# Test_Points.net
KiCad netlist of a schematic drawn in Altium Designer
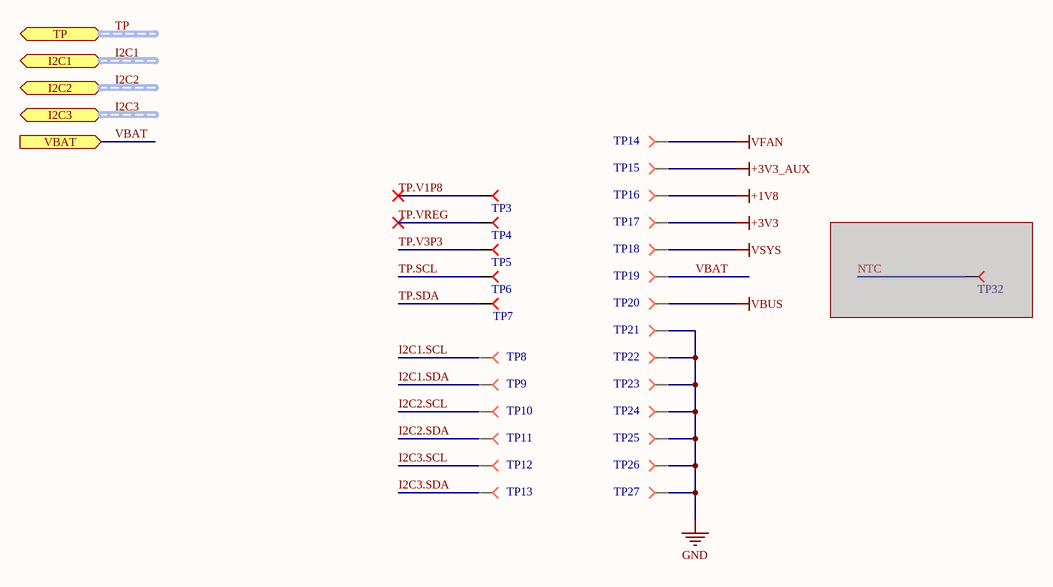
[diagram p0: Test_Points.SchDoc]

(export (version "E")
  (design (tool "Eeschema 10.0.6"))
  (components
    (comp (ref "TP3")
      (value "Test Point Pad")
      (footprint "Testpoint")
      (description "Test Point. There is nothing to buy or mount.")
      (libsource (lib "BLDC_Motor_Driver") (part "Test Point Pad"))
    )
    (comp (ref "TP4")
      (value "Test Point Pad")
      (footprint "Testpoint")
      (description "Test Point. There is nothing to buy or mount.")
      (libsource (lib "BLDC_Motor_Driver") (part "Test Point Pad"))
    )
    (comp (ref "TP5")
      (value "Test Point Pad")
      (footprint "Testpoint")
      (description "Test Point. There is nothing to buy or mount.")
      (libsource (lib "BLDC_Motor_Driver") (part "Test Point Pad"))
    )
    (comp (ref "TP6")
      (value "Test Point Pad")
      (footprint "Testpoint")
      (description "Test Point. There is nothing to buy or mount.")
      (libsource (lib "BLDC_Motor_Driver") (part "Test Point Pad"))
    )
    (comp (ref "TP7")
      (value "Test Point Pad")
      (footprint "Testpoint")
      (description "Test Point. There is nothing to buy or mount.")
      (libsource (lib "BLDC_Motor_Driver") (part "Test Point Pad"))
    )
    (comp (ref "TP8")
      (value "Test Point Pad")
      (footprint "Testpoint")
      (description "Test Point. There is nothing to buy or mount.")
      (libsource (lib "") (part "Test Point Pad_2"))
    )
    (comp (ref "TP9")
      (value "Test Point Pad")
      (footprint "Testpoint")
      (description "Test Point. There is nothing to buy or mount.")
      (libsource (lib "") (part "Test Point Pad_2"))
    )
    (comp (ref "TP10")
      (value "Test Point Pad")
      (footprint "Testpoint")
      (description "Test Point. There is nothing to buy or mount.")
      (libsource (lib "") (part "Test Point Pad_2"))
    )
    (comp (ref "TP11")
      (value "Test Point Pad")
      (footprint "Testpoint")
      (description "Test Point. There is nothing to buy or mount.")
      (libsource (lib "") (part "Test Point Pad_2"))
    )
    (comp (ref "TP12")
      (value "Test Point Pad")
      (footprint "Testpoint")
      (description "Test Point. There is nothing to buy or mount.")
      (libsource (lib "") (part "Test Point Pad_2"))
    )
    (comp (ref "TP13")
      (value "Test Point Pad")
      (footprint "Testpoint")
      (description "Test Point. There is nothing to buy or mount.")
      (libsource (lib "") (part "Test Point Pad_2"))
    )
    (comp (ref "TP14")
      (value "Test Point Pad")
      (footprint "Testpoint")
      (description "Test Point. There is nothing to buy or mount.")
      (libsource (lib "") (part "Test Point Pad_1"))
    )
    (comp (ref "TP15")
      (value "Test Point Pad")
      (footprint "Testpoint")
      (description "Test Point. There is nothing to buy or mount.")
      (libsource (lib "") (part "Test Point Pad_1"))
    )
    (comp (ref "TP16")
      (value "Test Point Pad")
      (footprint "Testpoint")
      (description "Test Point. There is nothing to buy or mount.")
      (libsource (lib "") (part "Test Point Pad_1"))
    )
    (comp (ref "TP17")
      (value "Test Point Pad")
      (footprint "Testpoint")
      (description "Test Point. There is nothing to buy or mount.")
      (libsource (lib "") (part "Test Point Pad_1"))
    )
    (comp (ref "TP18")
      (value "Test Point Pad")
      (footprint "Testpoint")
      (description "Test Point. There is nothing to buy or mount.")
      (libsource (lib "") (part "Test Point Pad_1"))
    )
    (comp (ref "TP19")
      (value "Test Point Pad")
      (footprint "Testpoint")
      (description "Test Point. There is nothing to buy or mount.")
      (libsource (lib "") (part "Test Point Pad_1"))
    )
    (comp (ref "TP20")
      (value "Test Point Pad")
      (footprint "Testpoint")
      (description "Test Point. There is nothing to buy or mount.")
      (libsource (lib "") (part "Test Point Pad_1"))
    )
    (comp (ref "TP21")
      (value "Test Point Pad")
      (footprint "Testpoint")
      (description "Test Point. There is nothing to buy or mount.")
      (libsource (lib "") (part "Test Point Pad_1"))
    )
    (comp (ref "TP22")
      (value "Test Point Pad")
      (footprint "Testpoint")
      (description "Test Point. There is nothing to buy or mount.")
      (libsource (lib "") (part "Test Point Pad_1"))
    )
    (comp (ref "TP23")
      (value "Test Point Pad")
      (footprint "Testpoint")
      (description "Test Point. There is nothing to buy or mount.")
      (libsource (lib "") (part "Test Point Pad_1"))
    )
    (comp (ref "TP24")
      (value "Test Point Pad")
      (footprint "Testpoint")
      (description "Test Point. There is nothing to buy or mount.")
      (libsource (lib "") (part "Test Point Pad_1"))
    )
    (comp (ref "TP25")
      (value "Test Point Pad")
      (footprint "Testpoint")
      (description "Test Point. There is nothing to buy or mount.")
      (libsource (lib "") (part "Test Point Pad_1"))
    )
    (comp (ref "TP26")
      (value "Test Point Pad")
      (footprint "Testpoint")
      (description "Test Point. There is nothing to buy or mount.")
      (libsource (lib "") (part "Test Point Pad_1"))
    )
    (comp (ref "TP27")
      (value "Test Point Pad")
      (footprint "Testpoint")
      (description "Test Point. There is nothing to buy or mount.")
      (libsource (lib "") (part "Test Point Pad_1"))
    )
    (comp (ref "TP32")
      (value "Test Point Pad")
      (footprint "Testpoint")
      (description "Test Point. There is nothing to buy or mount.")
      (libsource (lib "BLDC_Motor_Driver") (part "Test Point Pad"))
    )
  )
  (nets
    (net (code "5") (name "+1V8") (class "Default")
      (node (ref "TP16") (pin "1") (pinfunction "1_1") (pintype "passive"))
    )
    (net (code "6") (name "+3V3") (class "Default")
      (node (ref "TP17") (pin "1") (pinfunction "1_1") (pintype "passive"))
    )
    (net (code "7") (name "+3V3_AUX") (class "Default")
      (node (ref "TP15") (pin "1") (pinfunction "1_1") (pintype "passive"))
    )
    (net (code "8") (name "/I2C1.SCL") (class "Default")
      (node (ref "TP8") (pin "1") (pinfunction "1_1") (pintype "passive"))
    )
    (net (code "9") (name "/I2C1.SDA") (class "Default")
      (node (ref "TP9") (pin "1") (pinfunction "1_1") (pintype "passive"))
    )
    (net (code "10") (name "/I2C2.SCL") (class "Default")
      (node (ref "TP10") (pin "1") (pinfunction "1_1") (pintype "passive"))
    )
    (net (code "11") (name "/I2C2.SDA") (class "Default")
      (node (ref "TP11") (pin "1") (pinfunction "1_1") (pintype "passive"))
    )
    (net (code "12") (name "/I2C3.SCL") (class "Default")
      (node (ref "TP12") (pin "1") (pinfunction "1_1") (pintype "passive"))
    )
    (net (code "13") (name "/I2C3.SDA") (class "Default")
      (node (ref "TP13") (pin "1") (pinfunction "1_1") (pintype "passive"))
    )
    (net (code "14") (name "/NTC") (class "Default")
      (node (ref "TP32") (pin "1") (pinfunction "1_1") (pintype "passive"))
    )
    (net (code "15") (name "/TP.SCL") (class "Default")
      (node (ref "TP6") (pin "1") (pinfunction "1_1") (pintype "passive"))
    )
    (net (code "16") (name "/TP.SDA") (class "Default")
      (node (ref "TP7") (pin "1") (pinfunction "1_1") (pintype "passive"))
    )
    (net (code "17") (name "/TP.V1P8") (class "Default")
      (node (ref "TP3") (pin "1") (pinfunction "1_1") (pintype "passive+no_connect"))
    )
    (net (code "18") (name "/TP.V3P3") (class "Default")
      (node (ref "TP5") (pin "1") (pinfunction "1_1") (pintype "passive"))
    )
    (net (code "19") (name "/TP.VREG") (class "Default")
      (node (ref "TP4") (pin "1") (pinfunction "1_1") (pintype "passive+no_connect"))
    )
    (net (code "20") (name "/VBAT") (class "Default")
      (node (ref "TP19") (pin "1") (pinfunction "1_1") (pintype "passive"))
    )
    (net (code "25") (name "GND") (class "Default")
      (node (ref "TP21") (pin "1") (pinfunction "1_1") (pintype "passive"))
      (node (ref "TP22") (pin "1") (pinfunction "1_1") (pintype "passive"))
      (node (ref "TP23") (pin "1") (pinfunction "1_1") (pintype "passive"))
      (node (ref "TP24") (pin "1") (pinfunction "1_1") (pintype "passive"))
      (node (ref "TP25") (pin "1") (pinfunction "1_1") (pintype "passive"))
      (node (ref "TP26") (pin "1") (pinfunction "1_1") (pintype "passive"))
      (node (ref "TP27") (pin "1") (pinfunction "1_1") (pintype "passive"))
    )
    (net (code "26") (name "VBUS") (class "Default")
      (node (ref "TP20") (pin "1") (pinfunction "1_1") (pintype "passive"))
    )
    (net (code "27") (name "VFAN") (class "Default")
      (node (ref "TP14") (pin "1") (pinfunction "1_1") (pintype "passive"))
    )
    (net (code "28") (name "VSYS") (class "Default")
      (node (ref "TP18") (pin "1") (pinfunction "1_1") (pintype "passive"))
    )
  )
)
